# Outputs.net
KiCad netlist of a schematic drawn in Altium Designer
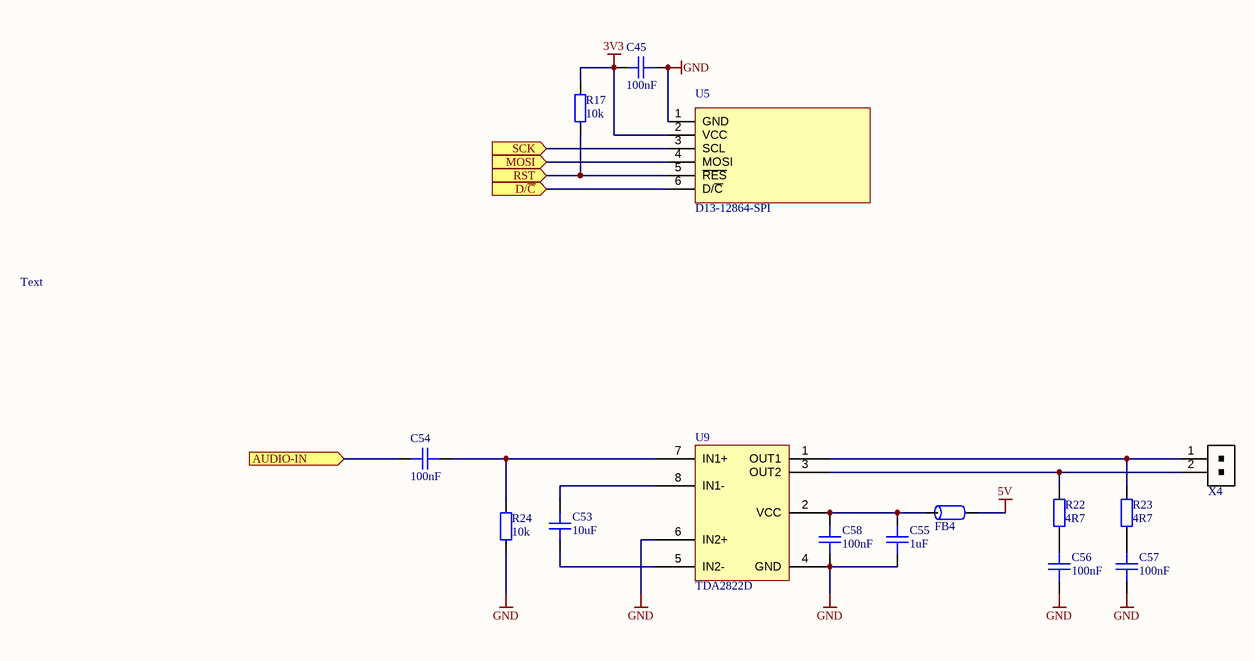
[diagram p0: Outputs.SchDoc]

(export (version "E")
  (design (tool "Eeschema 10.0.6"))
  (components
    (comp (ref "C45")
      (value "100nF")
      (footprint "CAP-0603")
      (description "Capacitor Non-Polar")
      (libsource (lib "MasterLib") (part "CAP - 0603"))
    )
    (comp (ref "C53")
      (value "10uF")
      (footprint "CAP-0805")
      (description "Capacitor Non-Polar")
      (libsource (lib "MasterLib") (part "CAP - 0805"))
    )
    (comp (ref "C54")
      (value "100nF")
      (footprint "CAP-0603")
      (description "Capacitor Non-Polar")
      (libsource (lib "MasterLib") (part "CAP - 0603"))
    )
    (comp (ref "C55")
      (value "1uF")
      (footprint "CAP-0805")
      (description "Capacitor Non-Polar")
      (libsource (lib "MasterLib") (part "CAP - 0805"))
    )
    (comp (ref "C56")
      (value "100nF")
      (footprint "CAP-0603")
      (description "Capacitor Non-Polar")
      (libsource (lib "MasterLib") (part "CAP - 0603"))
    )
    (comp (ref "C57")
      (value "100nF")
      (footprint "CAP-0603")
      (description "Capacitor Non-Polar")
      (libsource (lib "MasterLib") (part "CAP - 0603"))
    )
    (comp (ref "C58")
      (value "100nF")
      (footprint "CAP-0603")
      (description "Capacitor Non-Polar")
      (libsource (lib "MasterLib") (part "CAP - 0603"))
    )
    (comp (ref "FB4")
      (value "FB - 0603")
      (footprint "FB-0603")
      (description "Ferrit bead 0603")
      (libsource (lib "MasterLib") (part "FB - 0603"))
    )
    (comp (ref "R17")
      (value "10k")
      (footprint "RES-0603")
      (description "Resistor")
      (libsource (lib "MasterLib") (part "RES - 0603"))
    )
    (comp (ref "R22")
      (value "4R7")
      (footprint "RES-0603")
      (description "Resistor")
      (libsource (lib "MasterLib") (part "RES - 0603"))
    )
    (comp (ref "R23")
      (value "4R7")
      (footprint "RES-0603")
      (description "Resistor")
      (libsource (lib "MasterLib") (part "RES - 0603"))
    )
    (comp (ref "R24")
      (value "10k")
      (footprint "RES-0603")
      (description "Resistor")
      (libsource (lib "MasterLib") (part "RES - 0603"))
    )
    (comp (ref "U5")
      (value "D13-12864-SPI")
      (footprint "MISC-OLED DISPLAY-128x64")
      (description "1.3in 128x64 OLED, SPI interface, SH1106")
      (libsource (lib "MasterLib") (part "MISC - D13-12864-SPI"))
    )
    (comp (ref "U9")
      (value "TDA2822D")
      (footprint "IC-SOIC-8")
      (description "DUAL LOW-VOLTAGE POWER AMPLIFIER, 1W, 4-32 Ohm")
      (libsource (lib "MasterLib") (part "IC - TDA2822"))
    )
    (comp (ref "X4")
      (value "CONN - 2P -THT-JST 2.00mm")
      (footprint "CONN-2P-THT-RIGHT-JST 2.00mm")
      (description "1x2 pin THT connector")
      (libsource (lib "MasterLib") (part "CONN - 2P -THT-JST 2.00mm"))
    )
  )
  (nets
    (net (code "1") (name "/AUDIO-IN") (class "Default")
      (node (ref "C54") (pin "1") (pinfunction "1_1") (pintype "passive"))
    )
    (net (code "2") (name "/D{slash}~{C}") (class "Default")
      (node (ref "U5") (pin "6") (pinfunction "D/~{C}_6") (pintype "passive"))
    )
    (net (code "3") (name "/MOSI") (class "Default")
      (node (ref "U5") (pin "4") (pinfunction "MOSI_4") (pintype "passive"))
    )
    (net (code "4") (name "/RST") (class "Default")
      (node (ref "R17") (pin "1") (pinfunction "1_1") (pintype "passive"))
      (node (ref "U5") (pin "5") (pinfunction "~{RES}_5") (pintype "passive"))
    )
    (net (code "5") (name "/SCK") (class "Default")
      (node (ref "U5") (pin "3") (pinfunction "SCL_3") (pintype "passive"))
    )
    (net (code "6") (name "3V3") (class "Default")
      (node (ref "C45") (pin "2") (pinfunction "2_2") (pintype "passive"))
      (node (ref "R17") (pin "2") (pinfunction "2_2") (pintype "passive"))
      (node (ref "U5") (pin "2") (pinfunction "VCC_2") (pintype "passive"))
    )
    (net (code "7") (name "5V") (class "Default")
      (node (ref "FB4") (pin "2") (pinfunction "2_2") (pintype "passive"))
    )
    (net (code "8") (name "GND") (class "Default")
      (node (ref "C45") (pin "1") (pinfunction "1_1") (pintype "passive"))
      (node (ref "C55") (pin "1") (pinfunction "1_1") (pintype "passive"))
      (node (ref "C56") (pin "2") (pinfunction "2_2") (pintype "passive"))
      (node (ref "C57") (pin "2") (pinfunction "2_2") (pintype "passive"))
      (node (ref "C58") (pin "1") (pinfunction "1_1") (pintype "passive"))
      (node (ref "R24") (pin "1") (pinfunction "1_1") (pintype "passive"))
      (node (ref "U5") (pin "1") (pinfunction "GND_1") (pintype "passive"))
      (node (ref "U9") (pin "4") (pinfunction "GND_4") (pintype "passive"))
      (node (ref "U9") (pin "6") (pinfunction "IN2+_6") (pintype "passive"))
    )
    (net (code "9") (name "Net-(C56-Pad1)") (class "Default")
      (node (ref "C56") (pin "1") (pinfunction "1_1") (pintype "passive"))
      (node (ref "R22") (pin "1") (pinfunction "1_1") (pintype "passive"))
    )
    (net (code "10") (name "Net-(C57-Pad1)") (class "Default")
      (node (ref "C57") (pin "1") (pinfunction "1_1") (pintype "passive"))
      (node (ref "R23") (pin "1") (pinfunction "1_1") (pintype "passive"))
    )
    (net (code "11") (name "Net-(U9-IN1+)") (class "Default")
      (node (ref "C54") (pin "2") (pinfunction "2_2") (pintype "passive"))
      (node (ref "R24") (pin "2") (pinfunction "2_2") (pintype "passive"))
      (node (ref "U9") (pin "7") (pinfunction "IN1+_7") (pintype "passive"))
    )
    (net (code "12") (name "Net-(U9-IN1-)") (class "Default")
      (node (ref "C53") (pin "2") (pinfunction "2_2") (pintype "passive"))
      (node (ref "U9") (pin "8") (pinfunction "IN1-_8") (pintype "passive"))
    )
    (net (code "13") (name "Net-(U9-IN2-)") (class "Default")
      (node (ref "C53") (pin "1") (pinfunction "1_1") (pintype "passive"))
      (node (ref "U9") (pin "5") (pinfunction "IN2-_5") (pintype "passive"))
    )
    (net (code "14") (name "Net-(U9-OUT1)") (class "Default")
      (node (ref "R23") (pin "2") (pinfunction "2_2") (pintype "passive"))
      (node (ref "U9") (pin "1") (pinfunction "OUT1_1") (pintype "passive"))
      (node (ref "X4") (pin "1") (pinfunction "1_1") (pintype "passive"))
    )
    (net (code "15") (name "Net-(U9-OUT2)") (class "Default")
      (node (ref "R22") (pin "2") (pinfunction "2_2") (pintype "passive"))
      (node (ref "U9") (pin "3") (pinfunction "OUT2_3") (pintype "passive"))
      (node (ref "X4") (pin "2") (pinfunction "2_2") (pintype "passive"))
    )
    (net (code "16") (name "Net-(U9-VCC)") (class "Default")
      (node (ref "C55") (pin "2") (pinfunction "2_2") (pintype "passive"))
      (node (ref "C58") (pin "2") (pinfunction "2_2") (pintype "passive"))
      (node (ref "FB4") (pin "1") (pinfunction "1_1") (pintype "passive"))
      (node (ref "U9") (pin "2") (pinfunction "VCC_2") (pintype "passive"))
    )
  )
)
